# Quad-4layerV2.net
KiCad netlist of a schematic drawn in EAGLE
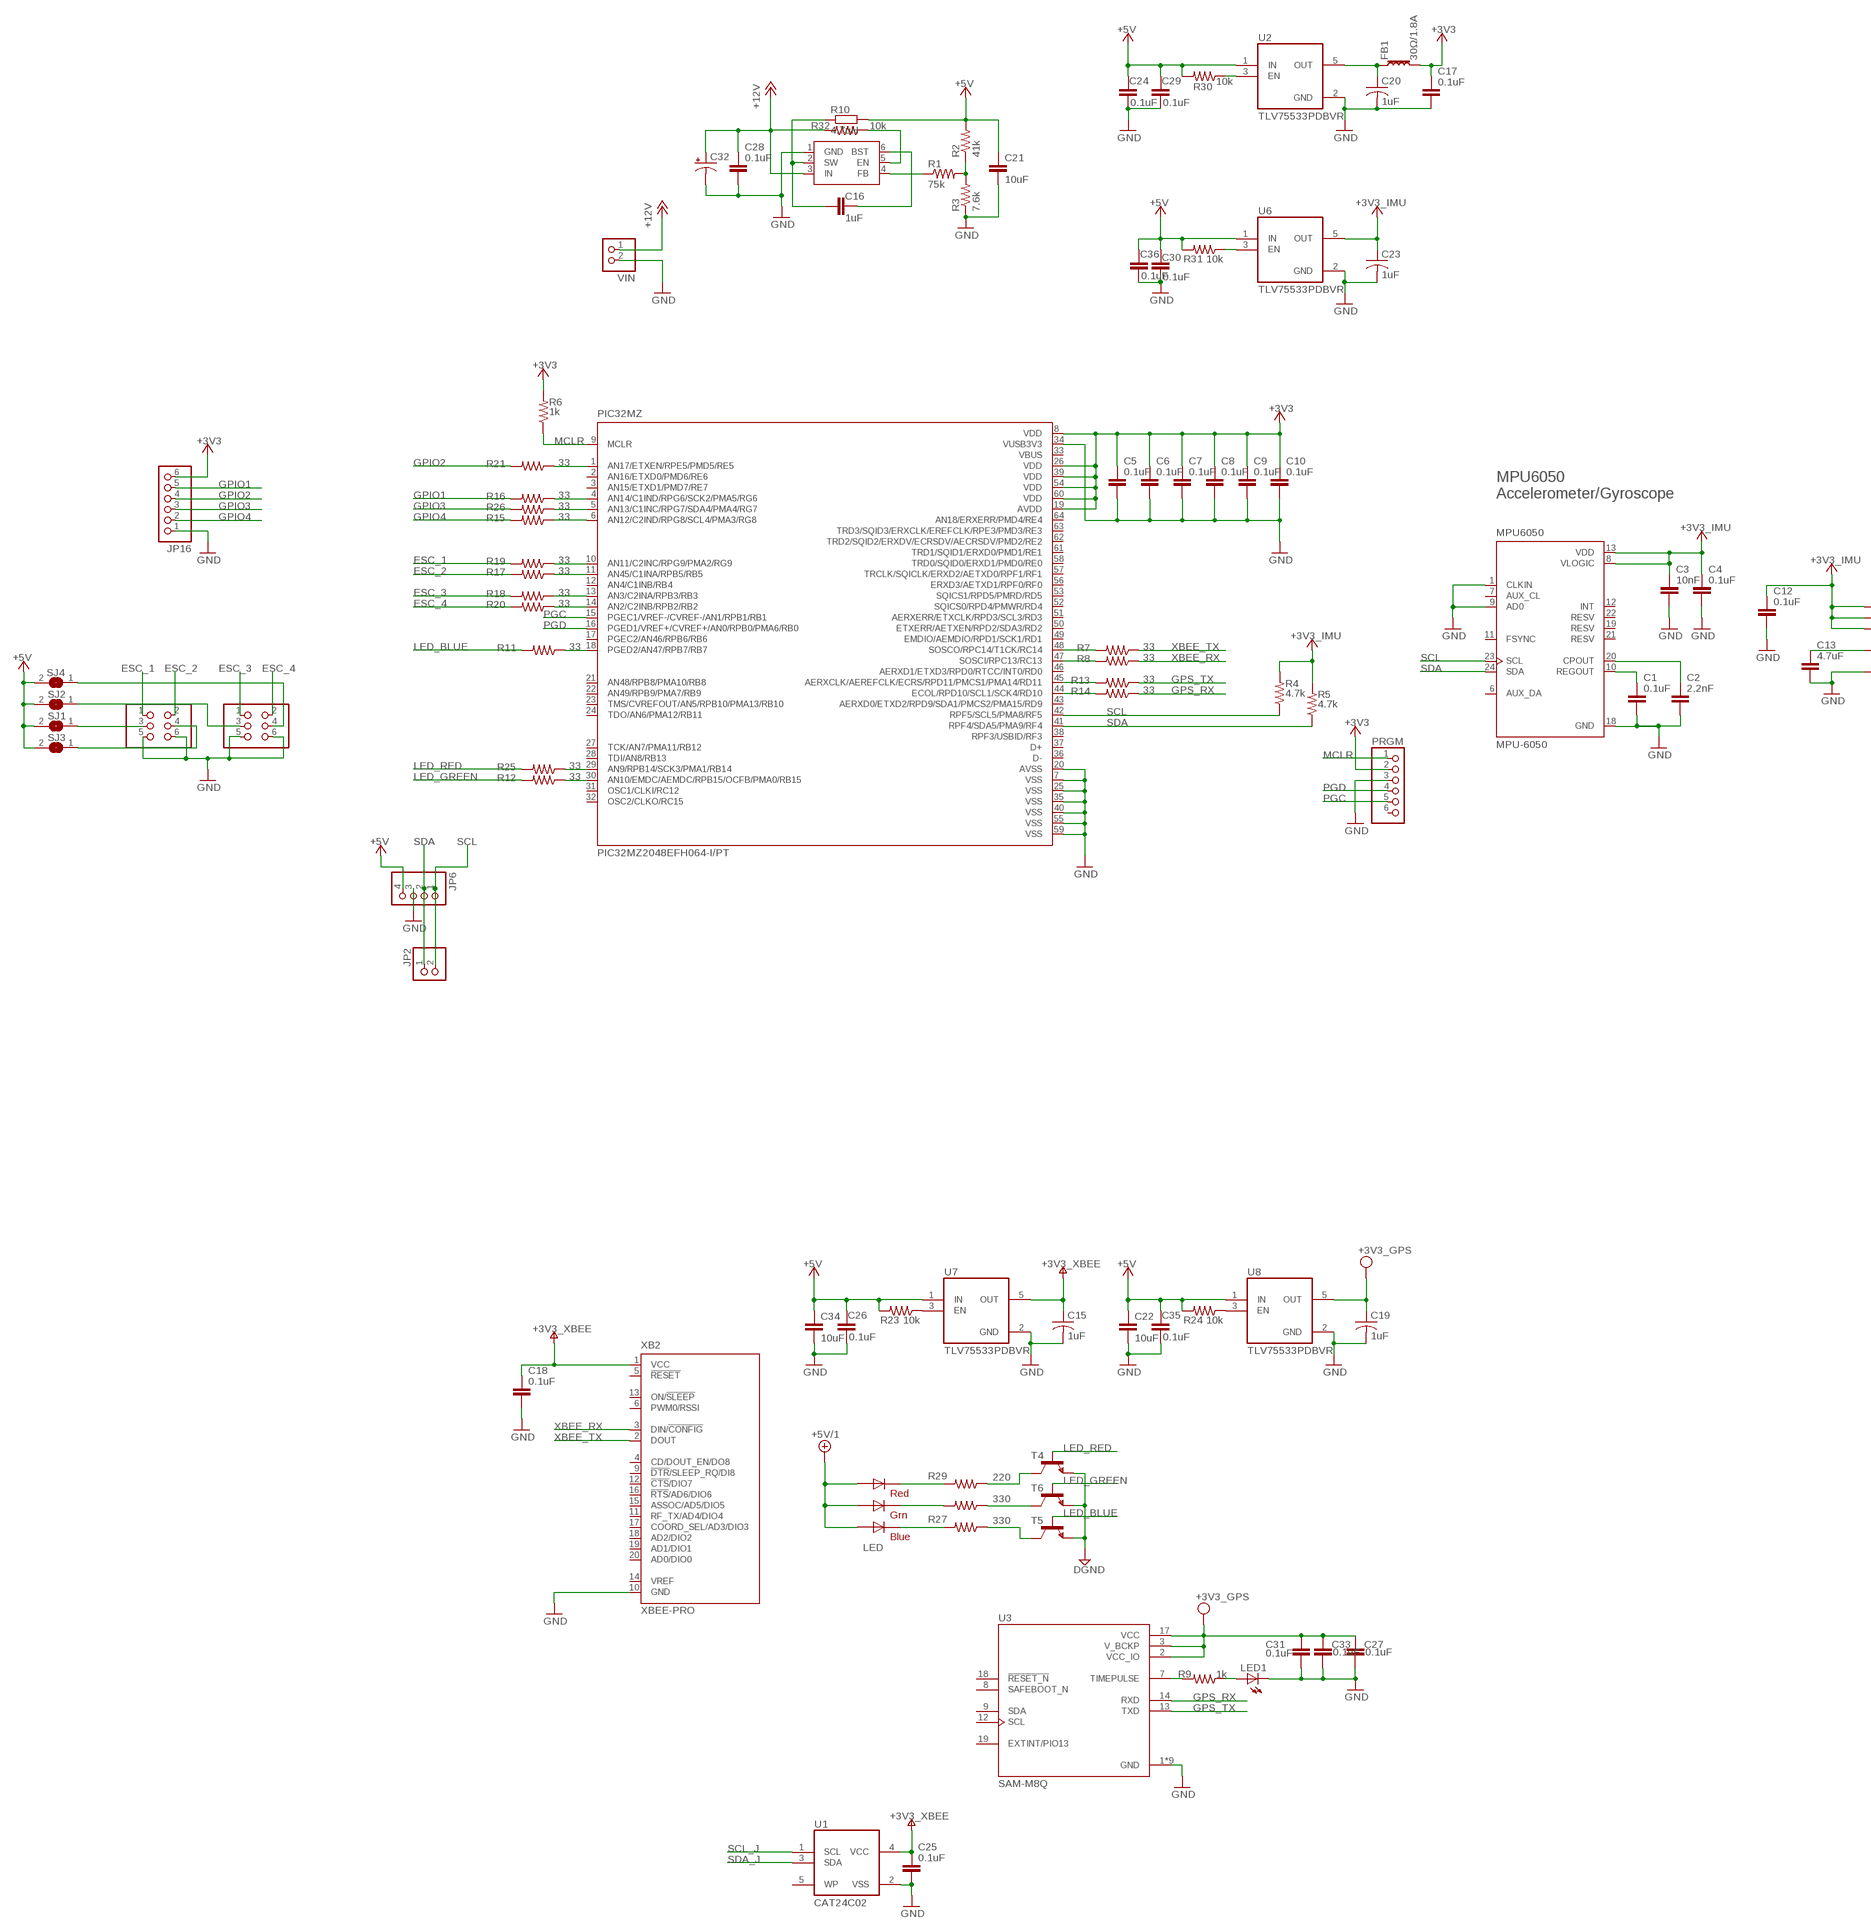
[diagram p0: schematic, sheet 1, part 1 of 2]
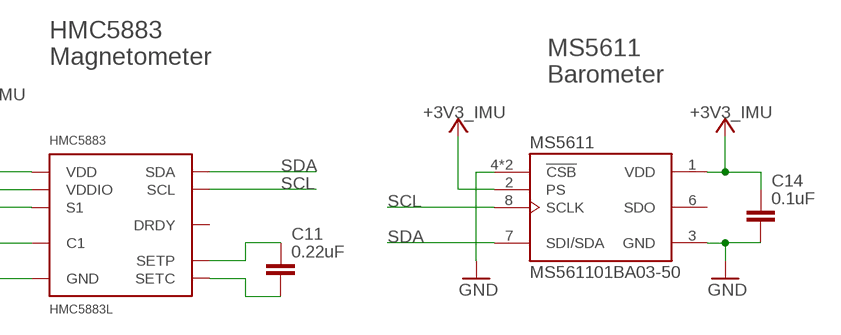
[diagram p1: schematic, sheet 1, part 2 of 2]

(export (version "E")
  (design (tool "Eeschema 10.0.6"))
  (components
    (comp (ref "C1")
      (value "0.1uF")
      (footprint "eagle-import:C0603")
      (libsource (lib "eagle-import") (part "C-EUC0603"))
    )
    (comp (ref "C2")
      (value "2.2nF")
      (footprint "eagle-import:C0603")
      (libsource (lib "eagle-import") (part "C-EUC0603"))
    )
    (comp (ref "C3")
      (value "10nF")
      (footprint "eagle-import:C0603")
      (libsource (lib "eagle-import") (part "C-EUC0603"))
    )
    (comp (ref "C4")
      (value "0.1uF")
      (footprint "eagle-import:C0603")
      (libsource (lib "eagle-import") (part "C-EUC0603"))
    )
    (comp (ref "C5")
      (value "0.1uF")
      (footprint "eagle-import:C0603")
      (libsource (lib "eagle-import") (part "C-EUC0603"))
    )
    (comp (ref "C6")
      (value "0.1uF")
      (footprint "eagle-import:C0603")
      (libsource (lib "eagle-import") (part "C-EUC0603"))
    )
    (comp (ref "C7")
      (value "0.1uF")
      (footprint "eagle-import:C0603")
      (libsource (lib "eagle-import") (part "C-EUC0603"))
    )
    (comp (ref "C8")
      (value "0.1uF")
      (footprint "eagle-import:C0603")
      (libsource (lib "eagle-import") (part "C-EUC0603"))
    )
    (comp (ref "C9")
      (value "0.1uF")
      (footprint "eagle-import:C0603")
      (libsource (lib "eagle-import") (part "C-EUC0603"))
    )
    (comp (ref "C10")
      (value "0.1uF")
      (footprint "eagle-import:C0603")
      (libsource (lib "eagle-import") (part "C-EUC0603"))
    )
    (comp (ref "C11")
      (value "0.22uF")
      (footprint "eagle-import:C0603")
      (libsource (lib "eagle-import") (part "C-EUC0603"))
    )
    (comp (ref "C12")
      (value "0.1uF")
      (footprint "eagle-import:C0603")
      (libsource (lib "eagle-import") (part "C-EUC0603"))
    )
    (comp (ref "C13")
      (value "4.7uF")
      (footprint "eagle-import:C0603")
      (libsource (lib "eagle-import") (part "C-EUC0603"))
    )
    (comp (ref "C14")
      (value "0.1uF")
      (footprint "eagle-import:C0603")
      (libsource (lib "eagle-import") (part "C-EUC0603"))
    )
    (comp (ref "C15")
      (value "1uF")
      (footprint "eagle-import:C0805")
      (libsource (lib "eagle-import") (part "C-USC0805"))
    )
    (comp (ref "C16")
      (value "1uF")
      (footprint "eagle-import:C0603")
      (libsource (lib "eagle-import") (part "C-EUC0603"))
    )
    (comp (ref "C17")
      (value "0.1uF")
      (footprint "eagle-import:C0603")
      (libsource (lib "eagle-import") (part "C-EUC0603"))
    )
    (comp (ref "C18")
      (value "0.1uF")
      (footprint "eagle-import:C0603")
      (libsource (lib "eagle-import") (part "C-EUC0603"))
    )
    (comp (ref "C19")
      (value "1uF")
      (footprint "eagle-import:C0805")
      (libsource (lib "eagle-import") (part "C-USC0805"))
    )
    (comp (ref "C20")
      (value "1uF")
      (footprint "eagle-import:C0805")
      (libsource (lib "eagle-import") (part "C-USC0805"))
    )
    (comp (ref "C21")
      (value "10uF")
      (footprint "eagle-import:C1206")
      (libsource (lib "eagle-import") (part "C-EUC1206"))
    )
    (comp (ref "C22")
      (value "10uF")
      (footprint "eagle-import:C1206")
      (libsource (lib "eagle-import") (part "C-EUC1206"))
    )
    (comp (ref "C23")
      (value "1uF")
      (footprint "eagle-import:C0805")
      (libsource (lib "eagle-import") (part "C-USC0805"))
    )
    (comp (ref "C24")
      (value "0.1uF")
      (footprint "eagle-import:C0603")
      (libsource (lib "eagle-import") (part "C-EUC0603"))
    )
    (comp (ref "C25")
      (value "0.1uF")
      (footprint "eagle-import:C0603")
      (libsource (lib "eagle-import") (part "C-EUC0603"))
    )
    (comp (ref "C26")
      (value "0.1uF")
      (footprint "eagle-import:C0603")
      (libsource (lib "eagle-import") (part "C-EUC0603"))
    )
    (comp (ref "C27")
      (value "0.1uF")
      (footprint "eagle-import:C0603")
      (libsource (lib "eagle-import") (part "C-EUC0603"))
    )
    (comp (ref "C28")
      (value "0.1uF")
      (footprint "eagle-import:C0603")
      (libsource (lib "eagle-import") (part "C-EUC0603"))
    )
    (comp (ref "C29")
      (value "0.1uF")
      (footprint "eagle-import:C0603")
      (libsource (lib "eagle-import") (part "C-EUC0603"))
    )
    (comp (ref "C30")
      (value "0.1uF")
      (footprint "eagle-import:C0603")
      (libsource (lib "eagle-import") (part "C-EUC0603"))
    )
    (comp (ref "C31")
      (value "0.1uF")
      (footprint "eagle-import:C0603")
      (libsource (lib "eagle-import") (part "C-EUC0603"))
    )
    (comp (ref "C32")
      (value "CPOL-US085CS-1AR")
      (footprint "eagle-import:085CS_1AR")
      (libsource (lib "eagle-import") (part "CPOL-US085CS-1AR"))
    )
    (comp (ref "C33")
      (value "0.1uF")
      (footprint "eagle-import:C0603")
      (libsource (lib "eagle-import") (part "C-EUC0603"))
    )
    (comp (ref "C34")
      (value "10uF")
      (footprint "eagle-import:C1206")
      (libsource (lib "eagle-import") (part "C-EUC1206"))
    )
    (comp (ref "C35")
      (value "0.1uF")
      (footprint "eagle-import:C0603")
      (libsource (lib "eagle-import") (part "C-EUC0603"))
    )
    (comp (ref "C36")
      (value "0.1uF")
      (footprint "eagle-import:C0603")
      (libsource (lib "eagle-import") (part "C-EUC0603"))
    )
    (comp (ref "FB1")
      (value "30Ω/1.8A")
      (footprint "eagle-import:0603")
      (libsource (lib "eagle-import") (part "FERRITE_BEAD-0603"))
    )
    (comp (ref "HMC5883")
      (value "HMC5883L")
      (footprint "eagle-import:LPCC-16")
      (fields (field (name "MF") "Honeywell Aerospace") (field (name "MP") "HMC5883L-T"))
      (libsource (lib "eagle-import") (part "HMC5883L"))
    )
    (comp (ref "JP2")
      (value "PINHD-1X2")
      (footprint "eagle-import:1X02")
      (libsource (lib "eagle-import") (part "PINHD-1X2"))
    )
    (comp (ref "JP4")
      (value "PINHD-2X3")
      (footprint "eagle-import:2X03")
      (libsource (lib "eagle-import") (part "PINHD-2X3"))
    )
    (comp (ref "JP5")
      (value "PINHD-2X3")
      (footprint "eagle-import:2X03")
      (libsource (lib "eagle-import") (part "PINHD-2X3"))
    )
    (comp (ref "JP6")
      (value "PINHD-1X4")
      (footprint "eagle-import:1X04")
      (libsource (lib "eagle-import") (part "PINHD-1X4"))
    )
    (comp (ref "JP16")
      (value "PINHD-1X6")
      (footprint "eagle-import:1X06")
      (libsource (lib "eagle-import") (part "PINHD-1X6"))
    )
    (comp (ref "LED")
      (value "RGBLED5050")
      (footprint "eagle-import:RGBLED5050")
      (libsource (lib "eagle-import") (part "RGBLED5050"))
    )
    (comp (ref "LED1")
      (value "LEDCHIPLED_0603")
      (footprint "eagle-import:CHIPLED_0603")
      (libsource (lib "eagle-import") (part "LEDCHIPLED_0603"))
    )
    (comp (ref "MPU6050")
      (value "MPU-6050")
      (footprint "eagle-import:QFN50P400X400X95-24N")
      (fields (field (name "MF") "TDK InvenSense"))
      (libsource (lib "eagle-import") (part "MPU-6050"))
    )
    (comp (ref "MS5611")
      (value "MS561101BA03-50")
      (footprint "eagle-import:SON125P500X300X100-8N")
      (fields (field (name "MF") "TE Connectivity"))
      (libsource (lib "eagle-import") (part "MS561101BA03-50"))
    )
    (comp (ref "PIC32MZ")
      (value "PIC32MZ2048EFH064-I/PT")
      (footprint "eagle-import:QFP50P1200X1200X120-64N")
      (fields
        (field (name "DIGI-KEY_PART_NUMBER") "PIC32MZ2048EFH064-I/PT-ND")
        (field (name "MF") "Microchip")
      )
      (libsource (lib "eagle-import") (part "PIC32MZ2048EFH064-I/PT"))
    )
    (comp (ref "PRGM")
      (value "PINHD-1X6")
      (footprint "eagle-import:1X06")
      (libsource (lib "eagle-import") (part "PINHD-1X6"))
    )
    (comp (ref "R1")
      (value "75k")
      (footprint "eagle-import:R0603")
      (libsource (lib "eagle-import") (part "R-US_R0603"))
    )
    (comp (ref "R2")
      (value "41k")
      (footprint "eagle-import:R0603")
      (libsource (lib "eagle-import") (part "R-US_R0603"))
    )
    (comp (ref "R3")
      (value "7.6k")
      (footprint "eagle-import:R0603")
      (libsource (lib "eagle-import") (part "R-US_R0603"))
    )
    (comp (ref "R4")
      (value "4.7k")
      (footprint "eagle-import:R0603")
      (libsource (lib "eagle-import") (part "R-US_R0603"))
    )
    (comp (ref "R5")
      (value "4.7k")
      (footprint "eagle-import:R0603")
      (libsource (lib "eagle-import") (part "R-US_R0603"))
    )
    (comp (ref "R6")
      (value "1k")
      (footprint "eagle-import:R0603")
      (libsource (lib "eagle-import") (part "R-US_R0603"))
    )
    (comp (ref "R7")
      (value "33")
      (footprint "eagle-import:R0603")
      (libsource (lib "eagle-import") (part "R-US_R0603"))
    )
    (comp (ref "R8")
      (value "33")
      (footprint "eagle-import:R0603")
      (libsource (lib "eagle-import") (part "R-US_R0603"))
    )
    (comp (ref "R9")
      (value "1k")
      (footprint "eagle-import:R0603")
      (libsource (lib "eagle-import") (part "R-US_R0603"))
    )
    (comp (ref "R10")
      (value "4.7uH")
      (footprint "eagle-import:R1210")
      (libsource (lib "eagle-import") (part "R-EU_R1210"))
    )
    (comp (ref "R11")
      (value "33")
      (footprint "eagle-import:R0603")
      (libsource (lib "eagle-import") (part "R-US_R0603"))
    )
    (comp (ref "R12")
      (value "33")
      (footprint "eagle-import:R0603")
      (libsource (lib "eagle-import") (part "R-US_R0603"))
    )
    (comp (ref "R13")
      (value "33")
      (footprint "eagle-import:R0603")
      (libsource (lib "eagle-import") (part "R-US_R0603"))
    )
    (comp (ref "R14")
      (value "33")
      (footprint "eagle-import:R0603")
      (libsource (lib "eagle-import") (part "R-US_R0603"))
    )
    (comp (ref "R15")
      (value "33")
      (footprint "eagle-import:R0603")
      (libsource (lib "eagle-import") (part "R-US_R0603"))
    )
    (comp (ref "R16")
      (value "33")
      (footprint "eagle-import:R0603")
      (libsource (lib "eagle-import") (part "R-US_R0603"))
    )
    (comp (ref "R17")
      (value "33")
      (footprint "eagle-import:R0603")
      (libsource (lib "eagle-import") (part "R-US_R0603"))
    )
    (comp (ref "R18")
      (value "33")
      (footprint "eagle-import:R0603")
      (libsource (lib "eagle-import") (part "R-US_R0603"))
    )
    (comp (ref "R19")
      (value "33")
      (footprint "eagle-import:R0603")
      (libsource (lib "eagle-import") (part "R-US_R0603"))
    )
    (comp (ref "R20")
      (value "33")
      (footprint "eagle-import:R0603")
      (libsource (lib "eagle-import") (part "R-US_R0603"))
    )
    (comp (ref "R21")
      (value "33")
      (footprint "eagle-import:R0603")
      (libsource (lib "eagle-import") (part "R-US_R0603"))
    )
    (comp (ref "R23")
      (value "10k")
      (footprint "eagle-import:R0603")
      (libsource (lib "eagle-import") (part "R-US_R0603"))
    )
    (comp (ref "R24")
      (value "10k")
      (footprint "eagle-import:R0603")
      (libsource (lib "eagle-import") (part "R-US_R0603"))
    )
    (comp (ref "R25")
      (value "33")
      (footprint "eagle-import:R0603")
      (libsource (lib "eagle-import") (part "R-US_R0603"))
    )
    (comp (ref "R26")
      (value "33")
      (footprint "eagle-import:R0603")
      (libsource (lib "eagle-import") (part "R-US_R0603"))
    )
    (comp (ref "R27")
      (value "330")
      (footprint "eagle-import:R0603")
      (libsource (lib "eagle-import") (part "R-US_R0603"))
    )
    (comp (ref "R28")
      (value "330")
      (footprint "eagle-import:R0603")
      (libsource (lib "eagle-import") (part "R-US_R0603"))
    )
    (comp (ref "R29")
      (value "220")
      (footprint "eagle-import:R0603")
      (libsource (lib "eagle-import") (part "R-US_R0603"))
    )
    (comp (ref "R30")
      (value "10k")
      (footprint "eagle-import:R0603")
      (libsource (lib "eagle-import") (part "R-US_R0603"))
    )
    (comp (ref "R31")
      (value "10k")
      (footprint "eagle-import:R0603")
      (libsource (lib "eagle-import") (part "R-US_R0603"))
    )
    (comp (ref "R32")
      (value "10k")
      (footprint "eagle-import:R0603")
      (libsource (lib "eagle-import") (part "R-US_R0603"))
    )
    (comp (ref "SJ1") (value "SJ") (footprint "eagle-import:SJ") (libsource (lib "eagle-import") (part "SJ")))
    (comp (ref "SJ2") (value "SJ") (footprint "eagle-import:SJ") (libsource (lib "eagle-import") (part "SJ")))
    (comp (ref "SJ3") (value "SJ") (footprint "eagle-import:SJ") (libsource (lib "eagle-import") (part "SJ")))
    (comp (ref "SJ4") (value "SJ") (footprint "eagle-import:SJ") (libsource (lib "eagle-import") (part "SJ")))
    (comp (ref "T4")
      (value "-NPN-SOT23-EBC")
      (footprint "eagle-import:SOT23-EBC")
      (libsource (lib "eagle-import") (part "-NPN-SOT23-EBC"))
    )
    (comp (ref "T5")
      (value "-NPN-SOT23-EBC")
      (footprint "eagle-import:SOT23-EBC")
      (libsource (lib "eagle-import") (part "-NPN-SOT23-EBC"))
    )
    (comp (ref "T6")
      (value "-NPN-SOT23-EBC")
      (footprint "eagle-import:SOT23-EBC")
      (libsource (lib "eagle-import") (part "-NPN-SOT23-EBC"))
    )
    (comp (ref "U$2")
      (value "AP65211A")
      (footprint "eagle-import:SOT95P280X140-6N")
      (libsource (lib "eagle-import") (part "AP65211A"))
    )
    (comp (ref "U1")
      (value "CAT24C02")
      (footprint "eagle-import:SOT95P280X145-5N")
      (fields (field (name "MF") "Texas Instruments") (field (name "MP") "TLV75533PDBVR"))
      (libsource (lib "eagle-import") (part "CAT24C02"))
    )
    (comp (ref "U2")
      (value "TLV75533PDBVR")
      (footprint "eagle-import:SOT95P280X145-5N")
      (fields (field (name "MF") "Texas Instruments"))
      (libsource (lib "eagle-import") (part "TLV75533PDBVR"))
    )
    (comp (ref "U3")
      (value "SAM-M8Q")
      (footprint "eagle-import:XCVR_SAM-M8Q")
      (fields (field (name "MF") "U-Blox America"))
      (libsource (lib "eagle-import") (part "SAM-M8Q"))
    )
    (comp (ref "U6")
      (value "TLV75533PDBVR")
      (footprint "eagle-import:SOT95P280X145-5N")
      (fields (field (name "MF") "Texas Instruments"))
      (libsource (lib "eagle-import") (part "TLV75533PDBVR"))
    )
    (comp (ref "U7")
      (value "TLV75533PDBVR")
      (footprint "eagle-import:SOT95P280X145-5N")
      (fields (field (name "MF") "Texas Instruments"))
      (libsource (lib "eagle-import") (part "TLV75533PDBVR"))
    )
    (comp (ref "U8")
      (value "TLV75533PDBVR")
      (footprint "eagle-import:SOT95P280X145-5N")
      (fields (field (name "MF") "Texas Instruments"))
      (libsource (lib "eagle-import") (part "TLV75533PDBVR"))
    )
    (comp (ref "VIN")
      (value "JST_2PIN-THM-RA")
      (footprint "eagle-import:JST-PH-2-THM-RA")
      (libsource (lib "eagle-import") (part "JST_2PIN-THM-RA"))
    )
    (comp (ref "XB2")
      (value "XBEE-PRO")
      (footprint "eagle-import:XBEE-PRO")
      (fields (field (name "MPN") "XBP24-AWI-001"))
      (libsource (lib "eagle-import") (part "XBEE-PRO"))
    )
  )
  (nets
    (net (code "1") (name "+3V3") (class "Default")
      (node (ref "C10") (pin "1") (pinfunction "1_1") (pintype "passive"))
      (node (ref "C17") (pin "1") (pinfunction "1_1") (pintype "passive"))
      (node (ref "C5") (pin "1") (pinfunction "1_1") (pintype "passive"))
      (node (ref "C6") (pin "1") (pinfunction "1_1") (pintype "passive"))
      (node (ref "C7") (pin "1") (pinfunction "1_1") (pintype "passive"))
      (node (ref "C8") (pin "1") (pinfunction "1_1") (pintype "passive"))
      (node (ref "C9") (pin "1") (pinfunction "1_1") (pintype "passive"))
      (node (ref "FB1") (pin "2") (pinfunction "2_2") (pintype "passive"))
      (node (ref "JP16") (pin "6") (pinfunction "6_6") (pintype "passive"))
      (node (ref "PIC32MZ") (pin "19") (pinfunction "AVDD_19") (pintype "power_in"))
      (node (ref "PIC32MZ") (pin "26") (pinfunction "VDD_26") (pintype "power_in"))
      (node (ref "PIC32MZ") (pin "39") (pinfunction "VDD_39") (pintype "power_in"))
      (node (ref "PIC32MZ") (pin "54") (pinfunction "VDD_54") (pintype "power_in"))
      (node (ref "PIC32MZ") (pin "60") (pinfunction "VDD_60") (pintype "power_in"))
      (node (ref "PIC32MZ") (pin "8") (pinfunction "VDD_8") (pintype "power_in"))
      (node (ref "PRGM") (pin "2") (pinfunction "2_2") (pintype "passive"))
      (node (ref "R6") (pin "2") (pinfunction "2_2") (pintype "passive"))
    )
    (net (code "2") (name "+3V3_GPS") (class "Default")
      (node (ref "C19") (pin "1") (pinfunction "1_1") (pintype "passive"))
      (node (ref "C27") (pin "1") (pinfunction "1_1") (pintype "passive"))
      (node (ref "C31") (pin "1") (pinfunction "1_1") (pintype "passive"))
      (node (ref "C33") (pin "1") (pinfunction "1_1") (pintype "passive"))
      (node (ref "U3") (pin "17") (pinfunction "VCC_17") (pintype "power_in"))
      (node (ref "U3") (pin "2") (pinfunction "VCC_IO_2") (pintype "power_in"))
      (node (ref "U3") (pin "3") (pinfunction "V_BCKP_3") (pintype "power_in"))
      (node (ref "U8") (pin "5") (pinfunction "OUT_5") (pintype "output"))
    )
    (net (code "3") (name "+3V3_IMU") (class "Default")
      (node (ref "C12") (pin "1") (pinfunction "1_1") (pintype "passive"))
      (node (ref "C14") (pin "1") (pinfunction "1_1") (pintype "passive"))
      (node (ref "C23") (pin "1") (pinfunction "1_1") (pintype "passive"))
      (node (ref "C3") (pin "1") (pinfunction "1_1") (pintype "passive"))
      (node (ref "C4") (pin "1") (pinfunction "1_1") (pintype "passive"))
      (node (ref "HMC5883") (pin "13") (pinfunction "VDDIO_13") (pintype "bidirectional"))
      (node (ref "HMC5883") (pin "2") (pinfunction "VDD_2") (pintype "bidirectional"))
      (node (ref "HMC5883") (pin "4") (pinfunction "S1_4") (pintype "bidirectional"))
      (node (ref "MPU6050") (pin "13") (pinfunction "VDD_13") (pintype "power_in"))
      (node (ref "MPU6050") (pin "8") (pinfunction "VLOGIC_8") (pintype "power_in"))
      (node (ref "MS5611") (pin "1") (pinfunction "VDD_1") (pintype "power_in"))
      (node (ref "MS5611") (pin "2") (pinfunction "PS_2") (pintype "input"))
      (node (ref "R4") (pin "2") (pinfunction "2_2") (pintype "passive"))
      (node (ref "R5") (pin "2") (pinfunction "2_2") (pintype "passive"))
      (node (ref "U6") (pin "5") (pinfunction "OUT_5") (pintype "output"))
    )
    (net (code "4") (name "+3V3_XBEE") (class "Default")
      (node (ref "C15") (pin "1") (pinfunction "1_1") (pintype "passive"))
      (node (ref "C18") (pin "1") (pinfunction "1_1") (pintype "passive"))
      (node (ref "C25") (pin "1") (pinfunction "1_1") (pintype "passive"))
      (node (ref "U1") (pin "4") (pinfunction "VCC_4") (pintype "output"))
      (node (ref "U7") (pin "5") (pinfunction "OUT_5") (pintype "output"))
      (node (ref "XB2") (pin "1") (pinfunction "VCC_1") (pintype "power_in"))
    )
    (net (code "5") (name "+5V") (class "Default")
      (node (ref "C21") (pin "1") (pinfunction "1_1") (pintype "passive"))
      (node (ref "C22") (pin "1") (pinfunction "1_1") (pintype "passive"))
      (node (ref "C24") (pin "1") (pinfunction "1_1") (pintype "passive"))
      (node (ref "C26") (pin "1") (pinfunction "1_1") (pintype "passive"))
      (node (ref "C29") (pin "1") (pinfunction "1_1") (pintype "passive"))
      (node (ref "C30") (pin "1") (pinfunction "1_1") (pintype "passive"))
      (node (ref "C34") (pin "1") (pinfunction "1_1") (pintype "passive"))
      (node (ref "C35") (pin "1") (pinfunction "1_1") (pintype "passive"))
      (node (ref "C36") (pin "1") (pinfunction "1_1") (pintype "passive"))
      (node (ref "JP6") (pin "4") (pinfunction "4_4") (pintype "passive"))
      (node (ref "R10") (pin "2") (pinfunction "2_2") (pintype "passive"))
      (node (ref "R2") (pin "2") (pinfunction "2_2") (pintype "passive"))
      (node (ref "R23") (pin "2") (pinfunction "2_2") (pintype "passive"))
      (node (ref "R24") (pin "2") (pinfunction "2_2") (pintype "passive"))
      (node (ref "R30") (pin "2") (pinfunction "2_2") (pintype "passive"))
      (node (ref "R31") (pin "2") (pinfunction "2_2") (pintype "passive"))
      (node (ref "SJ1") (pin "2") (pinfunction "2_2") (pintype "passive"))
      (node (ref "SJ2") (pin "2") (pinfunction "2_2") (pintype "passive"))
      (node (ref "SJ3") (pin "2") (pinfunction "2_2") (pintype "passive"))
      (node (ref "SJ4") (pin "2") (pinfunction "2_2") (pintype "passive"))
      (node (ref "U2") (pin "1") (pinfunction "IN_1") (pintype "input"))
      (node (ref "U6") (pin "1") (pinfunction "IN_1") (pintype "input"))
      (node (ref "U7") (pin "1") (pinfunction "IN_1") (pintype "input"))
      (node (ref "U8") (pin "1") (pinfunction "IN_1") (pintype "input"))
    )
    (net (code "6") (name "+5V{slash}1") (class "Default")
      (node (ref "LED") (pin "1") (pinfunction "GREEN_A_1") (pintype "bidirectional"))
      (node (ref "LED") (pin "2") (pinfunction "RED_A_2") (pintype "bidirectional"))
      (node (ref "LED") (pin "3") (pinfunction "BLUE_A_3") (pintype "bidirectional"))
    )
    (net (code "7") (name "+12V") (class "Default")
      (node (ref "C28") (pin "1") (pinfunction "1_1") (pintype "passive"))
      (node (ref "C32") (pin "+") (pinfunction "+_+") (pintype "passive"))
      (node (ref "R32") (pin "2") (pinfunction "2_2") (pintype "passive"))
      (node (ref "U$2") (pin "3") (pinfunction "IN_3") (pintype "bidirectional"))
      (node (ref "VIN") (pin "1") (pinfunction "2_1") (pintype "passive"))
    )
    (net (code "8") (name "/ESC_1") (class "Default")
      (node (ref "JP5") (pin "1") (pinfunction "1_1") (pintype "passive"))
      (node (ref "R19") (pin "2") (pinfunction "2_2") (pintype "passive"))
    )
    (net (code "9") (name "/ESC_2") (class "Default")
      (node (ref "JP5") (pin "2") (pinfunction "2_2") (pintype "passive"))
      (node (ref "R17") (pin "2") (pinfunction "2_2") (pintype "passive"))
    )
    (net (code "10") (name "/ESC_3") (class "Default")
      (node (ref "JP4") (pin "1") (pinfunction "1_1") (pintype "passive"))
      (node (ref "R18") (pin "2") (pinfunction "2_2") (pintype "passive"))
    )
    (net (code "11") (name "/ESC_4") (class "Default")
      (node (ref "JP4") (pin "2") (pinfunction "2_2") (pintype "passive"))
      (node (ref "R20") (pin "2") (pinfunction "2_2") (pintype "passive"))
    )
    (net (code "12") (name "/GPIO1") (class "Default")
      (node (ref "JP16") (pin "5") (pinfunction "5_5") (pintype "passive"))
      (node (ref "R16") (pin "2") (pinfunction "2_2") (pintype "passive"))
    )
    (net (code "13") (name "/GPIO2") (class "Default")
      (node (ref "JP16") (pin "4") (pinfunction "4_4") (pintype "passive"))
      (node (ref "R21") (pin "2") (pinfunction "2_2") (pintype "passive"))
    )
    (net (code "14") (name "/GPIO3") (class "Default")
      (node (ref "JP16") (pin "3") (pinfunction "3_3") (pintype "passive"))
      (node (ref "R26") (pin "2") (pinfunction "2_2") (pintype "passive"))
    )
    (net (code "15") (name "/GPIO4") (class "Default")
      (node (ref "JP16") (pin "2") (pinfunction "2_2") (pintype "passive"))
      (node (ref "R15") (pin "2") (pinfunction "2_2") (pintype "passive"))
    )
    (net (code "16") (name "/GPS_RX") (class "Default")
      (node (ref "R14") (pin "1") (pinfunction "1_1") (pintype "passive"))
      (node (ref "U3") (pin "14") (pinfunction "RXD_14") (pintype "input"))
    )
    (net (code "17") (name "/GPS_TX") (class "Default")
      (node (ref "R13") (pin "1") (pinfunction "1_1") (pintype "passive"))
      (node (ref "U3") (pin "13") (pinfunction "TXD_13") (pintype "output"))
    )
    (net (code "18") (name "/LED_BLUE") (class "Default")
      (node (ref "R11") (pin "2") (pinfunction "2_2") (pintype "passive"))
      (node (ref "T5") (pin "B") (pinfunction "B_B") (pintype "passive"))
    )
    (net (code "19") (name "/LED_GREEN") (class "Default")
      (node (ref "R12") (pin "2") (pinfunction "2_2") (pintype "passive"))
      (node (ref "T6") (pin "B") (pinfunction "B_B") (pintype "passive"))
    )
    (net (code "20") (name "/LED_RED") (class "Default")
      (node (ref "R25") (pin "2") (pinfunction "2_2") (pintype "passive"))
      (node (ref "T4") (pin "B") (pinfunction "B_B") (pintype "passive"))
    )
    (net (code "21") (name "/MCLR") (class "Default")
      (node (ref "PIC32MZ") (pin "9") (pinfunction "MCLR_9") (pintype "input"))
      (node (ref "PRGM") (pin "1") (pinfunction "1_1") (pintype "passive"))
      (node (ref "R6") (pin "1") (pinfunction "1_1") (pintype "passive"))
    )
    (net (code "22") (name "/PGC") (class "Default")
      (node (ref "PIC32MZ") (pin "15") (pinfunction "PGEC1/VREF-/CVREF-/AN1/RPB1/RB1_15") (pintype "bidirectional"))
      (node (ref "PRGM") (pin "5") (pinfunction "5_5") (pintype "passive"))
    )
    (net (code "23") (name "/PGD") (class "Default")
      (node (ref "PIC32MZ") (pin "16") (pinfunction "PGED1/VREF+/CVREF+/AN0/RPB0/PMA6/RB0_16") (pintype "bidirectional"))
      (node (ref "PRGM") (pin "4") (pinfunction "4_4") (pintype "passive"))
    )
    (net (code "24") (name "/SCL") (class "Default")
      (node (ref "HMC5883") (pin "1") (pinfunction "SCL_1") (pintype "bidirectional"))
      (node (ref "JP2") (pin "2") (pinfunction "2_2") (pintype "passive"))
      (node (ref "JP6") (pin "1") (pinfunction "1_1") (pintype "passive"))
      (node (ref "MPU6050") (pin "23") (pinfunction "SCL_23") (pintype "input"))
      (node (ref "MS5611") (pin "8") (pinfunction "SCLK_8") (pintype "input"))
      (node (ref "PIC32MZ") (pin "42") (pinfunction "RPF5/SCL5/PMA8/RF5_42") (pintype "bidirectional"))
      (node (ref "R4") (pin "1") (pinfunction "1_1") (pintype "passive"))
    )
    (net (code "25") (name "/SCL_J") (class "Default")
      (node (ref "U1") (pin "1") (pinfunction "SCL_1") (pintype "input"))
    )
    (net (code "26") (name "/SDA") (class "Default")
      (node (ref "HMC5883") (pin "16") (pinfunction "SDA_16") (pintype "bidirectional"))
      (node (ref "JP2") (pin "1") (pinfunction "1_1") (pintype "passive"))
      (node (ref "JP6") (pin "2") (pinfunction "2_2") (pintype "passive"))
      (node (ref "MPU6050") (pin "24") (pinfunction "SDA_24") (pintype "bidirectional"))
      (node (ref "MS5611") (pin "7") (pinfunction "SDI/SDA_7") (pintype "bidirectional"))
      (node (ref "PIC32MZ") (pin "41") (pinfunction "RPF4/SDA5/PMA9/RF4_41") (pintype "bidirectional"))
      (node (ref "R5") (pin "1") (pinfunction "1_1") (pintype "passive"))
    )
    (net (code "27") (name "/SDA_J") (class "Default")
      (node (ref "U1") (pin "3") (pinfunction "SDA_3") (pintype "input"))
    )
    (net (code "28") (name "/VBUS") (class "Default")
      (node (ref "PIC32MZ") (pin "33") (pinfunction "VBUS_33") (pintype "power_in"))
    )
    (net (code "29") (name "/XBEE_RX") (class "Default")
      (node (ref "R8") (pin "1") (pinfunction "1_1") (pintype "passive"))
      (node (ref "XB2") (pin "3") (pinfunction "DIN/~{CONFIG}_3") (pintype "input"))
    )
    (net (code "30") (name "/XBEE_TX") (class "Default")
      (node (ref "R7") (pin "1") (pinfunction "1_1") (pintype "passive"))
      (node (ref "XB2") (pin "2") (pinfunction "DOUT_2") (pintype "output"))
    )
    (net (code "31") (name "DGND") (class "Default")
      (node (ref "T4") (pin "E") (pinfunction "E_E") (pintype "passive"))
      (node (ref "T5") (pin "E") (pinfunction "E_E") (pintype "passive"))
      (node (ref "T6") (pin "E") (pinfunction "E_E") (pintype "passive"))
    )
    (net (code "32") (name "GND") (class "Default")
      (node (ref "C1") (pin "2") (pinfunction "2_2") (pintype "passive"))
      (node (ref "C10") (pin "2") (pinfunction "2_2") (pintype "passive"))
      (node (ref "C12") (pin "2") (pinfunction "2_2") (pintype "passive"))
      (node (ref "C13") (pin "2") (pinfunction "2_2") (pintype "passive"))
      (node (ref "C14") (pin "2") (pinfunction "2_2") (pintype "passive"))
      (node (ref "C15") (pin "2") (pinfunction "2_2") (pintype "passive"))
      (node (ref "C17") (pin "2") (pinfunction "2_2") (pintype "passive"))
      (node (ref "C18") (pin "2") (pinfunction "2_2") (pintype "passive"))
      (node (ref "C19") (pin "2") (pinfunction "2_2") (pintype "passive"))
      (node (ref "C2") (pin "2") (pinfunction "2_2") (pintype "passive"))
      (node (ref "C20") (pin "2") (pinfunction "2_2") (pintype "passive"))
      (node (ref "C21") (pin "2") (pinfunction "2_2") (pintype "passive"))
      (node (ref "C22") (pin "2") (pinfunction "2_2") (pintype "passive"))
      (node (ref "C23") (pin "2") (pinfunction "2_2") (pintype "passive"))
      (node (ref "C24") (pin "2") (pinfunction "2_2") (pintype "passive"))
      (node (ref "C25") (pin "2") (pinfunction "2_2") (pintype "passive"))
      (node (ref "C26") (pin "2") (pinfunction "2_2") (pintype "passive"))
      (node (ref "C27") (pin "2") (pinfunction "2_2") (pintype "passive"))
      (node (ref "C28") (pin "2") (pinfunction "2_2") (pintype "passive"))
      (node (ref "C29") (pin "2") (pinfunction "2_2") (pintype "passive"))
      (node (ref "C3") (pin "2") (pinfunction "2_2") (pintype "passive"))
      (node (ref "C30") (pin "2") (pinfunction "2_2") (pintype "passive"))
      (node (ref "C31") (pin "2") (pinfunction "2_2") (pintype "passive"))
      (node (ref "C32") (pin "-") (pinfunction "-_-") (pintype "passive"))
      (node (ref "C33") (pin "2") (pinfunction "2_2") (pintype "passive"))
      (node (ref "C34") (pin "2") (pinfunction "2_2") (pintype "passive"))
      (node (ref "C35") (pin "2") (pinfunction "2_2") (pintype "passive"))
      (node (ref "C36") (pin "2") (pinfunction "2_2") (pintype "passive"))
      (node (ref "C4") (pin "2") (pinfunction "2_2") (pintype "passive"))
      (node (ref "C5") (pin "2") (pinfunction "2_2") (pintype "passive"))
      (node (ref "C6") (pin "2") (pinfunction "2_2") (pintype "passive"))
      (node (ref "C7") (pin "2") (pinfunction "2_2") (pintype "passive"))
      (node (ref "C8") (pin "2") (pinfunction "2_2") (pintype "passive"))
      (node (ref "C9") (pin "2") (pinfunction "2_2") (pintype "passive"))
      (node (ref "HMC5883") (pin "11") (pinfunction "GND_11") (pintype "bidirectional"))
      (node (ref "HMC5883") (pin "9") (pinfunction "GND_9") (pintype "bidirectional"))
      (node (ref "JP16") (pin "1") (pinfunction "1_1") (pintype "passive"))
      (node (ref "JP4") (pin "5") (pinfunction "5_5") (pintype "passive"))
      (node (ref "JP4") (pin "6") (pinfunction "6_6") (pintype "passive"))
      (node (ref "JP5") (pin "5") (pinfunction "5_5") (pintype "passive"))
      (node (ref "JP5") (pin "6") (pinfunction "6_6") (pintype "passive"))
      (node (ref "JP6") (pin "3") (pinfunction "3_3") (pintype "passive"))
      (node (ref "LED1") (pin "C") (pinfunction "C_C") (pintype "passive"))
      (node (ref "MPU6050") (pin "1") (pinfunction "CLKIN_1") (pintype "input"))
      (node (ref "MPU6050") (pin "18") (pinfunction "GND_18") (pintype "power_in"))
      (node (ref "MPU6050") (pin "9") (pinfunction "AD0_9") (pintype "input"))
      (node (ref "MS5611") (pin "3") (pinfunction "GND_3") (pintype "power_in"))
      (node (ref "MS5611") (pin "4") (pinfunction "~{CSB}_4") (pintype "input"))
      (node (ref "MS5611") (pin "5") (pinfunction "~{CSB}_5") (pintype "input"))
      (node (ref "PIC32MZ") (pin "20") (pinfunction "AVSS_20") (pintype "power_in"))
      (node (ref "PIC32MZ") (pin "25") (pinfunction "VSS_25") (pintype "power_in"))
      (node (ref "PIC32MZ") (pin "34") (pinfunction "VUSB3V3_34") (pintype "power_in"))
      (node (ref "PIC32MZ") (pin "35") (pinfunction "VSS_35") (pintype "power_in"))
      (node (ref "PIC32MZ") (pin "40") (pinfunction "VSS_40") (pintype "power_in"))
      (node (ref "PIC32MZ") (pin "55") (pinfunction "VSS_55") (pintype "power_in"))
      (node (ref "PIC32MZ") (pin "59") (pinfunction "VSS_59") (pintype "power_in"))
      (node (ref "PIC32MZ") (pin "7") (pinfunction "VSS_7") (pintype "power_in"))
      (node (ref "PRGM") (pin "3") (pinfunction "3_3") (pintype "passive"))
      (node (ref "R3") (pin "1") (pinfunction "1_1") (pintype "passive"))
      (node (ref "U$2") (pin "1") (pinfunction "GND_1") (pintype "bidirectional"))
      (node (ref "U1") (pin "2") (pinfunction "VSS_2") (pintype "power_in"))
      (node (ref "U2") (pin "2") (pinfunction "GND_2") (pintype "power_in"))
      (node (ref "U3") (pin "1") (pinfunction "GND_1") (pintype "power_in"))
      (node (ref "U3") (pin "10") (pinfunction "GND_10") (pintype "power_in"))
      (node (ref "U3") (pin "11") (pinfunction "GND_11") (pintype "power_in"))
      (node (ref "U3") (pin "15") (pinfunction "GND_15") (pintype "power_in"))
      (node (ref "U3") (pin "16") (pinfunction "GND_16") (pintype "power_in"))
      (node (ref "U3") (pin "20") (pinfunction "GND_20") (pintype "power_in"))
      (node (ref "U3") (pin "4") (pinfunction "GND_4") (pintype "power_in"))
      (node (ref "U3") (pin "5") (pinfunction "GND_5") (pintype "power_in"))
      (node (ref "U3") (pin "6") (pinfunction "GND_6") (pintype "power_in"))
      (node (ref "U6") (pin "2") (pinfunction "GND_2") (pintype "power_in"))
      (node (ref "U7") (pin "2") (pinfunction "GND_2") (pintype "power_in"))
      (node (ref "U8") (pin "2") (pinfunction "GND_2") (pintype "power_in"))
      (node (ref "VIN") (pin "2") (pinfunction "1_2") (pintype "passive"))
      (node (ref "XB2") (pin "10") (pinfunction "GND_10") (pintype "power_in"))
    )
    (net (code "33") (name "Net-(HMC5883-C1)") (class "Default")
      (node (ref "C13") (pin "1") (pinfunction "1_1") (pintype "passive"))
      (node (ref "HMC5883") (pin "10") (pinfunction "C1_10") (pintype "bidirectional"))
    )
    (net (code "34") (name "Net-(HMC5883-SETC)") (class "Default")
      (node (ref "C11") (pin "2") (pinfunction "2_2") (pintype "passive"))
      (node (ref "HMC5883") (pin "12") (pinfunction "SETC_12") (pintype "bidirectional"))
    )
    (net (code "35") (name "Net-(HMC5883-SETP)") (class "Default")
      (node (ref "C11") (pin "1") (pinfunction "1_1") (pintype "passive"))
      (node (ref "HMC5883") (pin "8") (pinfunction "SETP_8") (pintype "bidirectional"))
    )
    (net (code "36") (name "Net-(JP4-Pad3)") (class "Default")
      (node (ref "JP4") (pin "3") (pinfunction "3_3") (pintype "passive"))
      (node (ref "SJ2") (pin "1") (pinfunction "1_1") (pintype "passive"))
    )
    (net (code "37") (name "Net-(JP4-Pad4)") (class "Default")
      (node (ref "JP4") (pin "4") (pinfunction "4_4") (pintype "passive"))
      (node (ref "SJ4") (pin "1") (pinfunction "1_1") (pintype "passive"))
    )
    (net (code "38") (name "Net-(JP5-Pad3)") (class "Default")
      (node (ref "JP5") (pin "3") (pinfunction "3_3") (pintype "passive"))
      (node (ref "SJ1") (pin "1") (pinfunction "1_1") (pintype "passive"))
    )
    (net (code "39") (name "Net-(JP5-Pad4)") (class "Default")
      (node (ref "JP5") (pin "4") (pinfunction "4_4") (pintype "passive"))
      (node (ref "SJ3") (pin "1") (pinfunction "1_1") (pintype "passive"))
    )
    (net (code "40") (name "Net-(LED-BLUE_C)") (class "Default")
      (node (ref "LED") (pin "4") (pinfunction "BLUE_C_4") (pintype "bidirectional"))
      (node (ref "R27") (pin "2") (pinfunction "2_2") (pintype "passive"))
    )
    (net (code "41") (name "Net-(LED-GREEN_C)") (class "Default")
      (node (ref "LED") (pin "6") (pinfunction "GREEN_C_6") (pintype "bidirectional"))
      (node (ref "R28") (pin "2") (pinfunction "2_2") (pintype "passive"))
    )
    (net (code "42") (name "Net-(LED-RED_C)") (class "Default")
      (node (ref "LED") (pin "5") (pinfunction "RED_C_5") (pintype "bidirectional"))
      (node (ref "R29") (pin "2") (pinfunction "2_2") (pintype "passive"))
    )
    (net (code "43") (name "Net-(LED1-PadA)") (class "Default")
      (node (ref "LED1") (pin "A") (pinfunction "A_A") (pintype "passive"))
      (node (ref "R9") (pin "1") (pinfunction "1_1") (pintype "passive"))
    )
    (net (code "44") (name "Net-(MPU6050-CPOUT)") (class "Default")
      (node (ref "C2") (pin "1") (pinfunction "1_1") (pintype "passive"))
      (node (ref "MPU6050") (pin "20") (pinfunction "CPOUT_20") (pintype "passive"))
    )
    (net (code "45") (name "Net-(MPU6050-REGOUT)") (class "Default")
      (node (ref "C1") (pin "1") (pinfunction "1_1") (pintype "passive"))
      (node (ref "MPU6050") (pin "10") (pinfunction "REGOUT_10") (pintype "passive"))
    )
    (net (code "46") (name "Net-(PIC32MZ-AERXCLK{slash}AEREFCLK{slash}ECRS{slash}RPD11{slash}PMCS1{slash}PMA14{slash}RD11)") (class "Default")
      (node (ref "PIC32MZ") (pin "45") (pinfunction "AERXCLK/AEREFCLK/ECRS/RPD11/PMCS1/PMA14/RD11_45") (pintype "bidirectional"))
      (node (ref "R13") (pin "2") (pinfunction "2_2") (pintype "passive"))
    )
    (net (code "47") (name "Net-(PIC32MZ-AN2{slash}C2INB{slash}RPB2{slash}RB2)") (class "Default")
      (node (ref "PIC32MZ") (pin "14") (pinfunction "AN2/C2INB/RPB2/RB2_14") (pintype "bidirectional"))
      (node (ref "R20") (pin "1") (pinfunction "1_1") (pintype "passive"))
    )
    (net (code "48") (name "Net-(PIC32MZ-AN3{slash}C2INA{slash}RPB3{slash}RB3)") (class "Default")
      (node (ref "PIC32MZ") (pin "13") (pinfunction "AN3/C2INA/RPB3/RB3_13") (pintype "bidirectional"))
      (node (ref "R18") (pin "1") (pinfunction "1_1") (pintype "passive"))
    )
    (net (code "49") (name "Net-(PIC32MZ-AN9{slash}RPB14{slash}SCK3{slash}PMA1{slash}RB14)") (class "Default")
      (node (ref "PIC32MZ") (pin "29") (pinfunction "AN9/RPB14/SCK3/PMA1/RB14_29") (pintype "bidirectional"))
      (node (ref "R25") (pin "1") (pinfunction "1_1") (pintype "passive"))
    )
    (net (code "50") (name "Net-(PIC32MZ-AN10{slash}EMDC{slash}AEMDC{slash}RPB15{slash}OCFB{slash}PMA0{slash}RB15)") (class "Default")
      (node (ref "PIC32MZ") (pin "30") (pinfunction "AN10/EMDC/AEMDC/RPB15/OCFB/PMA0/RB15_30") (pintype "bidirectional"))
      (node (ref "R12") (pin "1") (pinfunction "1_1") (pintype "passive"))
    )
    (net (code "51") (name "Net-(PIC32MZ-AN11{slash}C2INC{slash}RPG9{slash}PMA2{slash}RG9)") (class "Default")
      (node (ref "PIC32MZ") (pin "10") (pinfunction "AN11/C2INC/RPG9/PMA2/RG9_10") (pintype "bidirectional"))
      (node (ref "R19") (pin "1") (pinfunction "1_1") (pintype "passive"))
    )
    (net (code "52") (name "Net-(PIC32MZ-AN12{slash}C2IND{slash}RPG8{slash}SCL4{slash}PMA3{slash}RG8)") (class "Default")
      (node (ref "PIC32MZ") (pin "6") (pinfunction "AN12/C2IND/RPG8/SCL4/PMA3/RG8_6") (pintype "bidirectional"))
      (node (ref "R15") (pin "1") (pinfunction "1_1") (pintype "passive"))
    )
    (net (code "53") (name "Net-(PIC32MZ-AN13{slash}C1INC{slash}RPG7{slash}SDA4{slash}PMA4{slash}RG7)") (class "Default")
      (node (ref "PIC32MZ") (pin "5") (pinfunction "AN13/C1INC/RPG7/SDA4/PMA4/RG7_5") (pintype "bidirectional"))
      (node (ref "R26") (pin "1") (pinfunction "1_1") (pintype "passive"))
    )
    (net (code "54") (name "Net-(PIC32MZ-AN14{slash}C1IND{slash}RPG6{slash}SCK2{slash}PMA5{slash}RG6)") (class "Default")
      (node (ref "PIC32MZ") (pin "4") (pinfunction "AN14/C1IND/RPG6/SCK2/PMA5/RG6_4") (pintype "bidirectional"))
      (node (ref "R16") (pin "1") (pinfunction "1_1") (pintype "passive"))
    )
    (net (code "55") (name "Net-(PIC32MZ-AN17{slash}ETXEN{slash}RPE5{slash}PMD5{slash}RE5)") (class "Default")
      (node (ref "PIC32MZ") (pin "1") (pinfunction "AN17/ETXEN/RPE5/PMD5/RE5_1") (pintype "bidirectional"))
      (node (ref "R21") (pin "1") (pinfunction "1_1") (pintype "passive"))
    )
    (net (code "56") (name "Net-(PIC32MZ-AN45{slash}C1INA{slash}RPB5{slash}RB5)") (class "Default")
      (node (ref "PIC32MZ") (pin "11") (pinfunction "AN45/C1INA/RPB5/RB5_11") (pintype "bidirectional"))
      (node (ref "R17") (pin "1") (pinfunction "1_1") (pintype "passive"))
    )
    (net (code "57") (name "Net-(PIC32MZ-ECOL{slash}RPD10{slash}SCL1{slash}SCK4{slash}RD10)") (class "Default")
      (node (ref "PIC32MZ") (pin "44") (pinfunction "ECOL/RPD10/SCL1/SCK4/RD10_44") (pintype "bidirectional"))
      (node (ref "R14") (pin "2") (pinfunction "2_2") (pintype "passive"))
    )
    (net (code "58") (name "Net-(PIC32MZ-PGED2{slash}AN47{slash}RPB7{slash}RB7)") (class "Default")
      (node (ref "PIC32MZ") (pin "18") (pinfunction "PGED2/AN47/RPB7/RB7_18") (pintype "bidirectional"))
      (node (ref "R11") (pin "1") (pinfunction "1_1") (pintype "passive"))
    )
    (net (code "59") (name "Net-(PIC32MZ-SOSCI{slash}RPC13{slash}RC13)") (class "Default")
      (node (ref "PIC32MZ") (pin "47") (pinfunction "SOSCI/RPC13/RC13_47") (pintype "bidirectional"))
      (node (ref "R8") (pin "2") (pinfunction "2_2") (pintype "passive"))
    )
    (net (code "60") (name "Net-(PIC32MZ-SOSCO{slash}RPC14{slash}T1CK{slash}RC14)") (class "Default")
      (node (ref "PIC32MZ") (pin "48") (pinfunction "SOSCO/RPC14/T1CK/RC14_48") (pintype "bidirectional"))
      (node (ref "R7") (pin "2") (pinfunction "2_2") (pintype "passive"))
    )
    (net (code "61") (name "Net-(R1-Pad2)") (class "Default")
      (node (ref "R1") (pin "2") (pinfunction "2_2") (pintype "passive"))
      (node (ref "R2") (pin "1") (pinfunction "1_1") (pintype "passive"))
      (node (ref "R3") (pin "2") (pinfunction "2_2") (pintype "passive"))
    )
    (net (code "62") (name "Net-(R27-Pad1)") (class "Default")
      (node (ref "R27") (pin "1") (pinfunction "1_1") (pintype "passive"))
      (node (ref "T5") (pin "C") (pinfunction "C_C") (pintype "passive"))
    )
    (net (code "63") (name "Net-(R28-Pad1)") (class "Default")
      (node (ref "R28") (pin "1") (pinfunction "1_1") (pintype "passive"))
      (node (ref "T6") (pin "C") (pinfunction "C_C") (pintype "passive"))
    )
    (net (code "64") (name "Net-(R29-Pad1)") (class "Default")
      (node (ref "R29") (pin "1") (pinfunction "1_1") (pintype "passive"))
      (node (ref "T4") (pin "C") (pinfunction "C_C") (pintype "passive"))
    )
    (net (code "65") (name "Net-(U$2-BST)") (class "Default")
      (node (ref "C16") (pin "2") (pinfunction "2_2") (pintype "passive"))
      (node (ref "U$2") (pin "6") (pinfunction "BST_6") (pintype "bidirectional"))
    )
    (net (code "66") (name "Net-(U$2-EN)") (class "Default")
      (node (ref "R32") (pin "1") (pinfunction "1_1") (pintype "passive"))
      (node (ref "U$2") (pin "5") (pinfunction "EN_5") (pintype "bidirectional"))
    )
    (net (code "67") (name "Net-(U$2-FB)") (class "Default")
      (node (ref "R1") (pin "1") (pinfunction "1_1") (pintype "passive"))
      (node (ref "U$2") (pin "4") (pinfunction "FB_4") (pintype "bidirectional"))
    )
    (net (code "68") (name "Net-(U$2-SW)") (class "Default")
      (node (ref "C16") (pin "1") (pinfunction "1_1") (pintype "passive"))
      (node (ref "R10") (pin "1") (pinfunction "1_1") (pintype "passive"))
      (node (ref "U$2") (pin "2") (pinfunction "SW_2") (pintype "bidirectional"))
    )
    (net (code "69") (name "Net-(U2-EN)") (class "Default")
      (node (ref "R30") (pin "1") (pinfunction "1_1") (pintype "passive"))
      (node (ref "U2") (pin "3") (pinfunction "EN_3") (pintype "input"))
    )
    (net (code "70") (name "Net-(U2-OUT)") (class "Default")
      (node (ref "C20") (pin "1") (pinfunction "1_1") (pintype "passive"))
      (node (ref "FB1") (pin "1") (pinfunction "1_1") (pintype "passive"))
      (node (ref "U2") (pin "5") (pinfunction "OUT_5") (pintype "output"))
    )
    (net (code "71") (name "Net-(U3-TIMEPULSE)") (class "Default")
      (node (ref "R9") (pin "2") (pinfunction "2_2") (pintype "passive"))
      (node (ref "U3") (pin "7") (pinfunction "TIMEPULSE_7") (pintype "output"))
    )
    (net (code "72") (name "Net-(U6-EN)") (class "Default")
      (node (ref "R31") (pin "1") (pinfunction "1_1") (pintype "passive"))
      (node (ref "U6") (pin "3") (pinfunction "EN_3") (pintype "input"))
    )
    (net (code "73") (name "Net-(U7-EN)") (class "Default")
      (node (ref "R23") (pin "1") (pinfunction "1_1") (pintype "passive"))
      (node (ref "U7") (pin "3") (pinfunction "EN_3") (pintype "input"))
    )
    (net (code "74") (name "Net-(U8-EN)") (class "Default")
      (node (ref "R24") (pin "1") (pinfunction "1_1") (pintype "passive"))
      (node (ref "U8") (pin "3") (pinfunction "EN_3") (pintype "input"))
    )
    (net (code "75") (name "unconnected-(HMC5883-DRDY-Pad15)") (class "Default")
      (node (ref "HMC5883") (pin "15") (pinfunction "DRDY_15") (pintype "bidirectional"))
    )
    (net (code "76") (name "unconnected-(MPU6050-AUX_CL-Pad7)") (class "Default")
      (node (ref "MPU6050") (pin "7") (pinfunction "AUX_CL_7") (pintype "input"))
    )
    (net (code "77") (name "unconnected-(MPU6050-AUX_DA-Pad6)") (class "Default")
      (node (ref "MPU6050") (pin "6") (pinfunction "AUX_DA_6") (pintype "bidirectional"))
    )
    (net (code "78") (name "unconnected-(MPU6050-FSYNC-Pad11)") (class "Default")
      (node (ref "MPU6050") (pin "11") (pinfunction "FSYNC_11") (pintype "input"))
    )
    (net (code "79") (name "unconnected-(MPU6050-INT-Pad12)") (class "Default")
      (node (ref "MPU6050") (pin "12") (pinfunction "INT_12") (pintype "output"))
    )
    (net (code "80") (name "unconnected-(MPU6050-RESV-Pad19)") (class "Default")
      (node (ref "MPU6050") (pin "19") (pinfunction "RESV_19") (pintype "passive"))
    )
    (net (code "81") (name "unconnected-(MPU6050-RESV-Pad21)") (class "Default")
      (node (ref "MPU6050") (pin "21") (pinfunction "RESV_21") (pintype "passive"))
    )
    (net (code "82") (name "unconnected-(MPU6050-RESV-Pad22)") (class "Default")
      (node (ref "MPU6050") (pin "22") (pinfunction "RESV_22") (pintype "passive"))
    )
    (net (code "83") (name "unconnected-(MS5611-SDO-Pad6)") (class "Default")
      (node (ref "MS5611") (pin "6") (pinfunction "SDO_6") (pintype "output"))
    )
    (net (code "84") (name "unconnected-(PIC32MZ-AERXD0{slash}ETXD2{slash}RPD9{slash}SDA1{slash}PMCS2{slash}PMA15{slash}RD9-Pad43)") (class "Default")
      (node (ref "PIC32MZ") (pin "43") (pinfunction "AERXD0/ETXD2/RPD9/SDA1/PMCS2/PMA15/RD9_43") (pintype "bidirectional"))
    )
    (net (code "85") (name "unconnected-(PIC32MZ-AERXD1{slash}ETXD3{slash}RPD0{slash}RTCC{slash}INT0{slash}RD0-Pad46)") (class "Default")
      (node (ref "PIC32MZ") (pin "46") (pinfunction "AERXD1/ETXD3/RPD0/RTCC/INT0/RD0_46") (pintype "bidirectional"))
    )
    (net (code "86") (name "unconnected-(PIC32MZ-AERXERR{slash}ETXCLK{slash}RPD3{slash}SCL3{slash}RD3-Pad51)") (class "Default")
      (node (ref "PIC32MZ") (pin "51") (pinfunction "AERXERR/ETXCLK/RPD3/SCL3/RD3_51") (pintype "bidirectional"))
    )
    (net (code "87") (name "unconnected-(PIC32MZ-AN4{slash}C1INB{slash}RB4-Pad12)") (class "Default")
      (node (ref "PIC32MZ") (pin "12") (pinfunction "AN4/C1INB/RB4_12") (pintype "bidirectional"))
    )
    (net (code "88") (name "unconnected-(PIC32MZ-AN15{slash}ETXD1{slash}PMD7{slash}RE7-Pad3)") (class "Default")
      (node (ref "PIC32MZ") (pin "3") (pinfunction "AN15/ETXD1/PMD7/RE7_3") (pintype "bidirectional"))
    )
    (net (code "89") (name "unconnected-(PIC32MZ-AN16{slash}ETXD0{slash}PMD6{slash}RE6-Pad2)") (class "Default")
      (node (ref "PIC32MZ") (pin "2") (pinfunction "AN16/ETXD0/PMD6/RE6_2") (pintype "bidirectional"))
    )
    (net (code "90") (name "unconnected-(PIC32MZ-AN18{slash}ERXERR{slash}PMD4{slash}RE4-Pad64)") (class "Default")
      (node (ref "PIC32MZ") (pin "64") (pinfunction "AN18/ERXERR/PMD4/RE4_64") (pintype "bidirectional"))
    )
    (net (code "91") (name "unconnected-(PIC32MZ-AN48{slash}RPB8{slash}PMA10{slash}RB8-Pad21)") (class "Default")
      (node (ref "PIC32MZ") (pin "21") (pinfunction "AN48/RPB8/PMA10/RB8_21") (pintype "bidirectional"))
    )
    (net (code "92") (name "unconnected-(PIC32MZ-AN49{slash}RPB9{slash}PMA7{slash}RB9-Pad22)") (class "Default")
      (node (ref "PIC32MZ") (pin "22") (pinfunction "AN49/RPB9/PMA7/RB9_22") (pintype "bidirectional"))
    )
    (net (code "93") (name "unconnected-(PIC32MZ-D+-Pad37)") (class "Default")
      (node (ref "PIC32MZ") (pin "37") (pinfunction "D+_37") (pintype "bidirectional"))
    )
    (net (code "94") (name "unconnected-(PIC32MZ-D--Pad36)") (class "Default")
      (node (ref "PIC32MZ") (pin "36") (pinfunction "D-_36") (pintype "bidirectional"))
    )
    (net (code "95") (name "unconnected-(PIC32MZ-EMDIO{slash}AEMDIO{slash}RPD1{slash}SCK1{slash}RD1-Pad49)") (class "Default")
      (node (ref "PIC32MZ") (pin "49") (pinfunction "EMDIO/AEMDIO/RPD1/SCK1/RD1_49") (pintype "bidirectional"))
    )
    (net (code "96") (name "unconnected-(PIC32MZ-ERXD3{slash}AETXD1{slash}RPF0{slash}RF0-Pad56)") (class "Default")
      (node (ref "PIC32MZ") (pin "56") (pinfunction "ERXD3/AETXD1/RPF0/RF0_56") (pintype "bidirectional"))
    )
    (net (code "97") (name "unconnected-(PIC32MZ-ETXERR{slash}AETXEN{slash}RPD2{slash}SDA3{slash}RD2-Pad50)") (class "Default")
      (node (ref "PIC32MZ") (pin "50") (pinfunction "ETXERR/AETXEN/RPD2/SDA3/RD2_50") (pintype "bidirectional"))
    )
    (net (code "98") (name "unconnected-(PIC32MZ-OSC1{slash}CLKI{slash}RC12-Pad31)") (class "Default")
      (node (ref "PIC32MZ") (pin "31") (pinfunction "OSC1/CLKI/RC12_31") (pintype "bidirectional"))
    )
    (net (code "99") (name "unconnected-(PIC32MZ-OSC2{slash}CLKO{slash}RC15-Pad32)") (class "Default")
      (node (ref "PIC32MZ") (pin "32") (pinfunction "OSC2/CLKO/RC15_32") (pintype "bidirectional"))
    )
    (net (code "100") (name "unconnected-(PIC32MZ-PGEC2{slash}AN46{slash}RPB6{slash}RB6-Pad17)") (class "Default")
      (node (ref "PIC32MZ") (pin "17") (pinfunction "PGEC2/AN46/RPB6/RB6_17") (pintype "bidirectional"))
    )
    (net (code "101") (name "unconnected-(PIC32MZ-RPF3{slash}USBID{slash}RF3-Pad38)") (class "Default")
      (node (ref "PIC32MZ") (pin "38") (pinfunction "RPF3/USBID/RF3_38") (pintype "bidirectional"))
    )
    (net (code "102") (name "unconnected-(PIC32MZ-SQICS0{slash}RPD4{slash}PMWR{slash}RD4-Pad52)") (class "Default")
      (node (ref "PIC32MZ") (pin "52") (pinfunction "SQICS0/RPD4/PMWR/RD4_52") (pintype "bidirectional"))
    )
    (net (code "103") (name "unconnected-(PIC32MZ-SQICS1{slash}RPD5{slash}PMRD{slash}RD5-Pad53)") (class "Default")
      (node (ref "PIC32MZ") (pin "53") (pinfunction "SQICS1/RPD5/PMRD/RD5_53") (pintype "bidirectional"))
    )
    (net (code "104") (name "unconnected-(PIC32MZ-TCK{slash}AN7{slash}PMA11{slash}RB12-Pad27)") (class "Default")
      (node (ref "PIC32MZ") (pin "27") (pinfunction "TCK/AN7/PMA11/RB12_27") (pintype "bidirectional"))
    )
    (net (code "105") (name "unconnected-(PIC32MZ-TDI{slash}AN8{slash}RB13-Pad28)") (class "Default")
      (node (ref "PIC32MZ") (pin "28") (pinfunction "TDI/AN8/RB13_28") (pintype "bidirectional"))
    )
    (net (code "106") (name "unconnected-(PIC32MZ-TDO{slash}AN6{slash}PMA12{slash}RB11-Pad24)") (class "Default")
      (node (ref "PIC32MZ") (pin "24") (pinfunction "TDO/AN6/PMA12/RB11_24") (pintype "bidirectional"))
    )
    (net (code "107") (name "unconnected-(PIC32MZ-TMS{slash}CVREFOUT{slash}AN5{slash}RPB10{slash}PMA13{slash}RB10-Pad23)") (class "Default")
      (node (ref "PIC32MZ") (pin "23") (pinfunction "TMS/CVREFOUT/AN5/RPB10/PMA13/RB10_23") (pintype "bidirectional"))
    )
    (net (code "108") (name "unconnected-(PIC32MZ-TRCLK{slash}SQICLK{slash}ERXD2{slash}AETXD0{slash}RPF1{slash}RF1-Pad57)") (class "Default")
      (node (ref "PIC32MZ") (pin "57") (pinfunction "TRCLK/SQICLK/ERXD2/AETXD0/RPF1/RF1_57") (pintype "bidirectional"))
    )
    (net (code "109") (name "unconnected-(PIC32MZ-TRD0{slash}SQID0{slash}ERXD1{slash}PMD0{slash}RE0-Pad58)") (class "Default")
      (node (ref "PIC32MZ") (pin "58") (pinfunction "TRD0/SQID0/ERXD1/PMD0/RE0_58") (pintype "bidirectional"))
    )
    (net (code "110") (name "unconnected-(PIC32MZ-TRD1{slash}SQID1{slash}ERXD0{slash}PMD1{slash}RE1-Pad61)") (class "Default")
      (node (ref "PIC32MZ") (pin "61") (pinfunction "TRD1/SQID1/ERXD0/PMD1/RE1_61") (pintype "bidirectional"))
    )
    (net (code "111") (name "unconnected-(PIC32MZ-TRD2{slash}SQID2{slash}ERXDV{slash}ECRSDV{slash}AECRSDV{slash}PMD2{slash}RE2-Pad62)") (class "Default")
      (node (ref "PIC32MZ") (pin "62") (pinfunction "TRD2/SQID2/ERXDV/ECRSDV/AECRSDV/PMD2/RE2_62") (pintype "bidirectional"))
    )
    (net (code "112") (name "unconnected-(PIC32MZ-TRD3{slash}SQID3{slash}ERXCLK{slash}EREFCLK{slash}RPE3{slash}PMD3{slash}RE3-Pad63)") (class "Default")
      (node (ref "PIC32MZ") (pin "63") (pinfunction "TRD3/SQID3/ERXCLK/EREFCLK/RPE3/PMD3/RE3_63") (pintype "bidirectional"))
    )
    (net (code "113") (name "unconnected-(PRGM-Pad6)") (class "Default")
      (node (ref "PRGM") (pin "6") (pinfunction "6_6") (pintype "passive"))
    )
    (net (code "114") (name "unconnected-(U1-WP-Pad5)") (class "Default")
      (node (ref "U1") (pin "5") (pinfunction "WP_5") (pintype "bidirectional"))
    )
    (net (code "115") (name "unconnected-(U3-EXTINT{slash}PIO13-Pad19)") (class "Default")
      (node (ref "U3") (pin "19") (pinfunction "EXTINT/PIO13_19") (pintype "input"))
    )
    (net (code "116") (name "unconnected-(U3-SAFEBOOT_N-Pad8)") (class "Default")
      (node (ref "U3") (pin "8") (pinfunction "SAFEBOOT_N_8") (pintype "input"))
    )
    (net (code "117") (name "unconnected-(U3-SCL-Pad12)") (class "Default")
      (node (ref "U3") (pin "12") (pinfunction "SCL_12") (pintype "input"))
    )
    (net (code "118") (name "unconnected-(U3-SDA-Pad9)") (class "Default")
      (node (ref "U3") (pin "9") (pinfunction "SDA_9") (pintype "bidirectional"))
    )
    (net (code "119") (name "unconnected-(U3-~{RESET_N}-Pad18)") (class "Default")
      (node (ref "U3") (pin "18") (pinfunction "~{RESET_N}_18") (pintype "input"))
    )
    (net (code "120") (name "unconnected-(XB2-AD0{slash}DIO0-Pad20)") (class "Default")
      (node (ref "XB2") (pin "20") (pinfunction "AD0/DIO0_20") (pintype "bidirectional"))
    )
    (net (code "121") (name "unconnected-(XB2-AD1{slash}DIO1-Pad19)") (class "Default")
      (node (ref "XB2") (pin "19") (pinfunction "AD1/DIO1_19") (pintype "bidirectional"))
    )
    (net (code "122") (name "unconnected-(XB2-AD2{slash}DIO2-Pad18)") (class "Default")
      (node (ref "XB2") (pin "18") (pinfunction "AD2/DIO2_18") (pintype "bidirectional"))
    )
    (net (code "123") (name "unconnected-(XB2-ASSOC{slash}AD5{slash}DIO5-Pad15)") (class "Default")
      (node (ref "XB2") (pin "15") (pinfunction "ASSOC/AD5/DIO5_15") (pintype "bidirectional"))
    )
    (net (code "124") (name "unconnected-(XB2-CD{slash}DOUT_EN{slash}DO8-Pad4)") (class "Default")
      (node (ref "XB2") (pin "4") (pinfunction "CD/DOUT_EN/DO8_4") (pintype "output"))
    )
    (net (code "125") (name "unconnected-(XB2-COORD_SEL{slash}AD3{slash}DIO3-Pad17)") (class "Default")
      (node (ref "XB2") (pin "17") (pinfunction "COORD_SEL/AD3/DIO3_17") (pintype "bidirectional"))
    )
    (net (code "126") (name "unconnected-(XB2-ON{slash}~{SLEEP}-Pad13)") (class "Default")
      (node (ref "XB2") (pin "13") (pinfunction "ON/~{SLEEP}_13") (pintype "output"))
    )
    (net (code "127") (name "unconnected-(XB2-PWM0{slash}RSSI-Pad6)") (class "Default")
      (node (ref "XB2") (pin "6") (pinfunction "PWM0/RSSI_6") (pintype "output"))
    )
    (net (code "128") (name "unconnected-(XB2-RF_TX{slash}AD4{slash}DIO4-Pad11)") (class "Default")
      (node (ref "XB2") (pin "11") (pinfunction "RF_TX/AD4/DIO4_11") (pintype "bidirectional"))
    )
    (net (code "129") (name "unconnected-(XB2-VREF-Pad14)") (class "Default")
      (node (ref "XB2") (pin "14") (pinfunction "VREF_14") (pintype "input"))
    )
    (net (code "130") (name "unconnected-(XB2-~{CTS}{slash}DIO7-Pad12)") (class "Default")
      (node (ref "XB2") (pin "12") (pinfunction "~{CTS}/DIO7_12") (pintype "bidirectional"))
    )
    (net (code "131") (name "unconnected-(XB2-~{DTR}{slash}SLEEP_RQ{slash}DI8-Pad9)") (class "Default")
      (node (ref "XB2") (pin "9") (pinfunction "~{DTR}/SLEEP_RQ/DI8_9") (pintype "bidirectional"))
    )
    (net (code "132") (name "unconnected-(XB2-~{RESET}-Pad5)") (class "Default")
      (node (ref "XB2") (pin "5") (pinfunction "~{RESET}_5") (pintype "input"))
    )
    (net (code "133") (name "unconnected-(XB2-~{RTS}{slash}AD6{slash}DIO6-Pad16)") (class "Default")
      (node (ref "XB2") (pin "16") (pinfunction "~{RTS}/AD6/DIO6_16") (pintype "bidirectional"))
    )
  )
)
